# Shift_registers_circuit.net
KiCad netlist of a schematic drawn in EAGLE
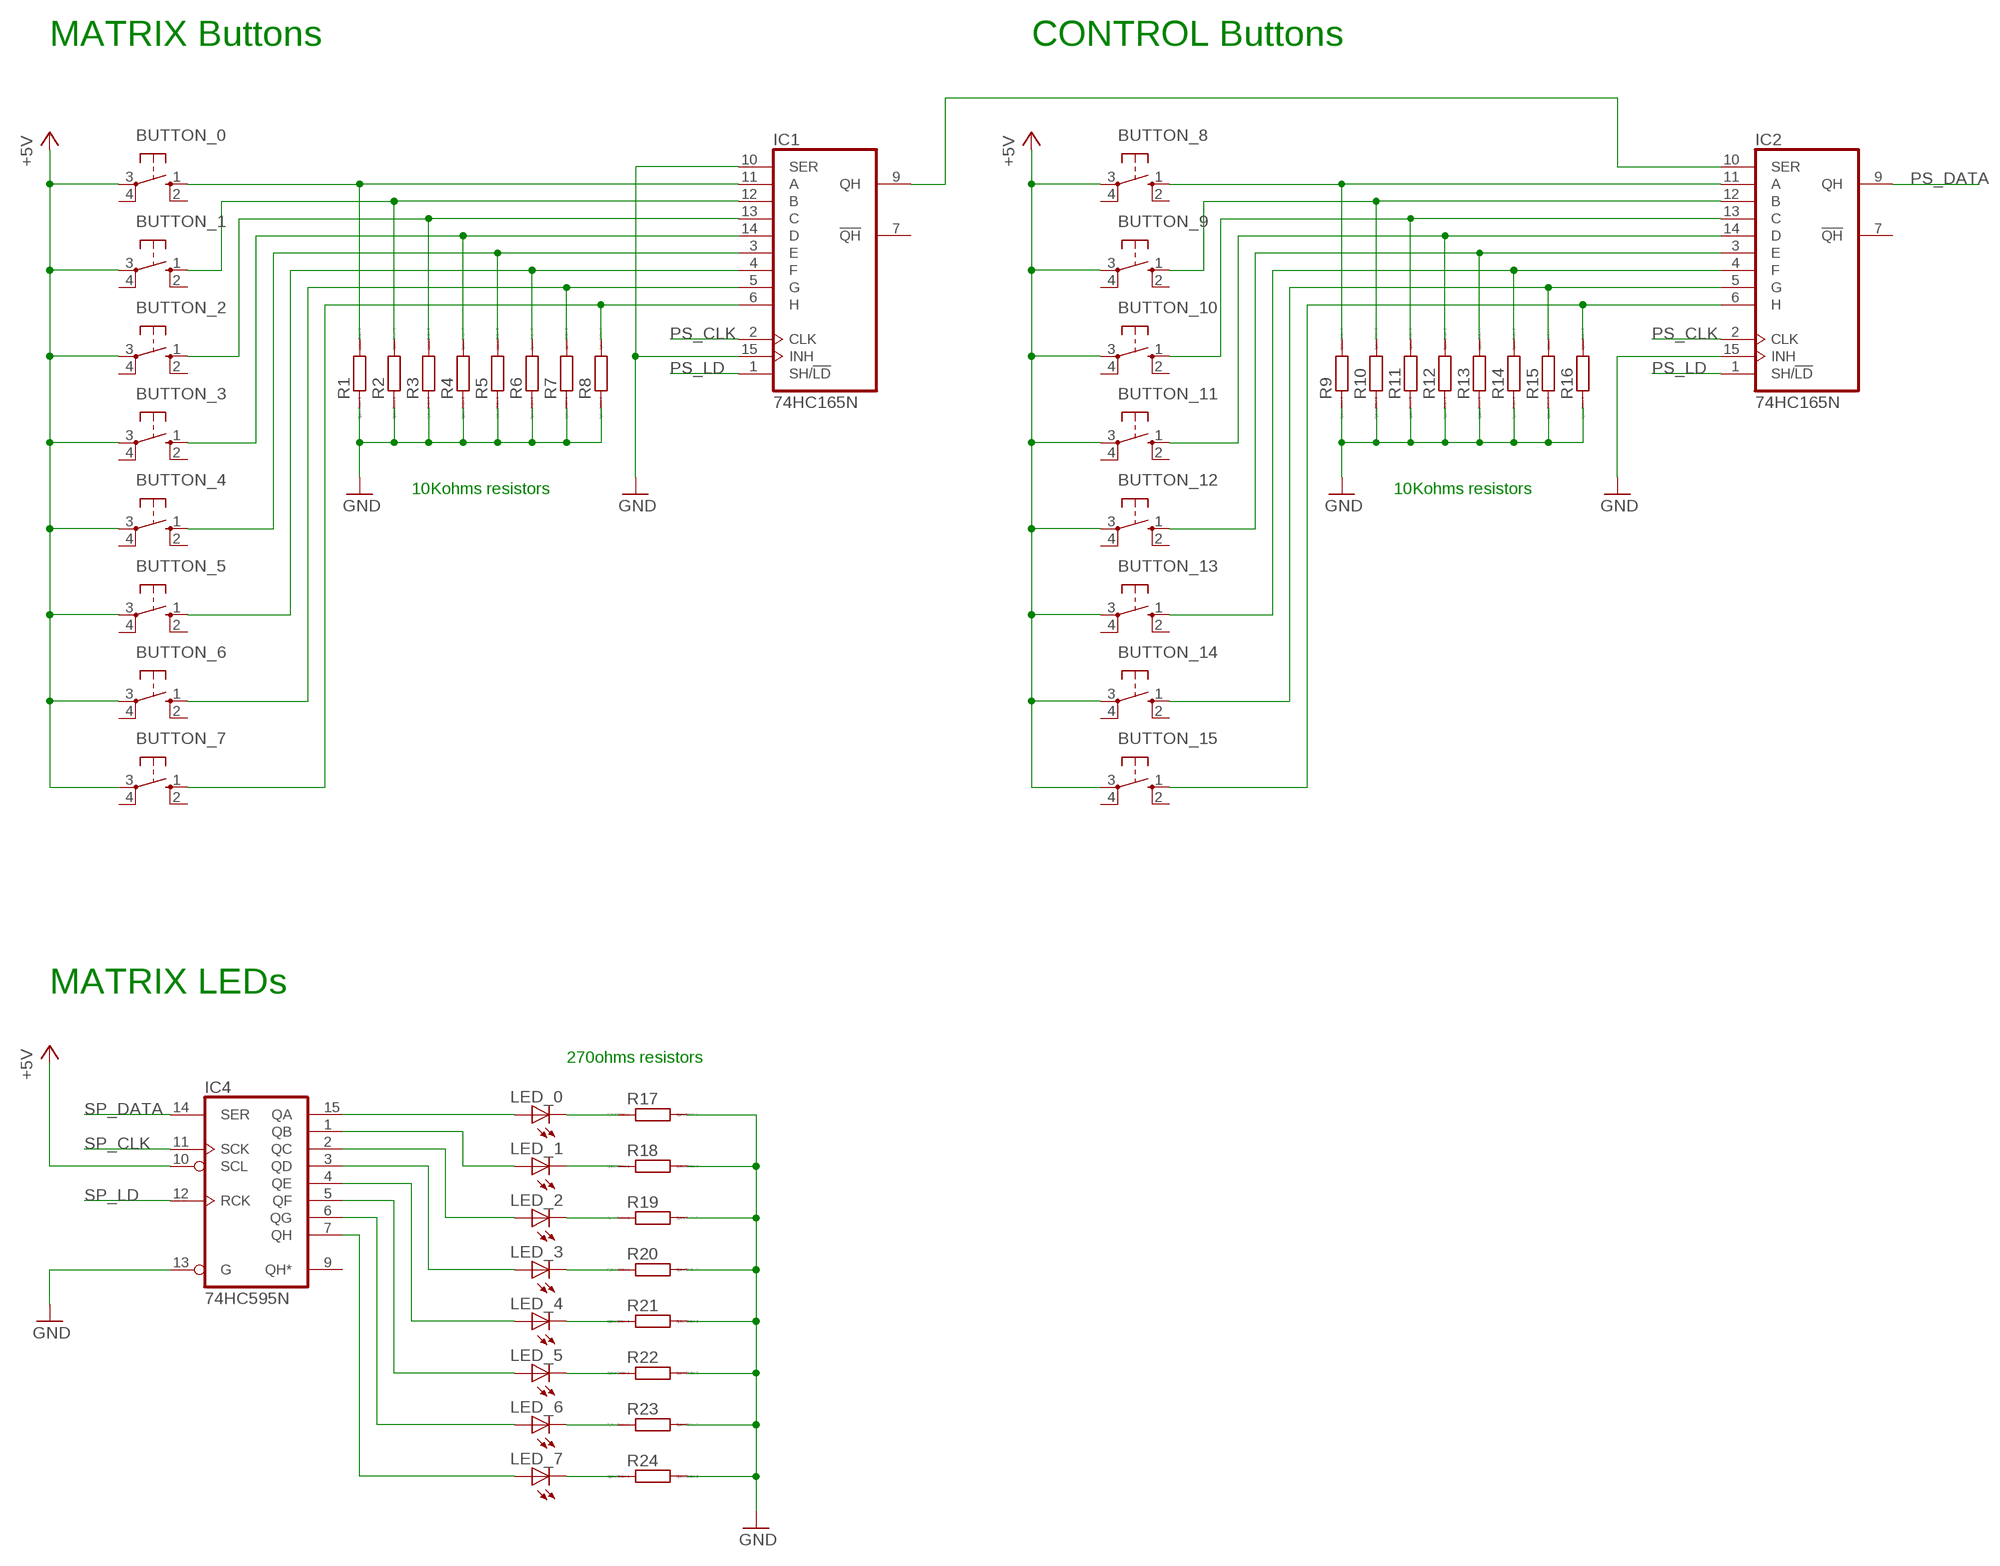
[diagram p0: schematic, sheet 1]

(export (version "E")
  (design (tool "Eeschema 10.0.6"))
  (components
    (comp (ref "BUTTON_0")
      (value "10-XX")
      (footprint "eagle-import:B3F-10XX")
      (fields (field (name "MPN") "B3F-1000"))
      (libsource (lib "eagle-import") (part "10-XX"))
    )
    (comp (ref "BUTTON_1")
      (value "10-XX")
      (footprint "eagle-import:B3F-10XX")
      (fields (field (name "MPN") "B3F-1000"))
      (libsource (lib "eagle-import") (part "10-XX"))
    )
    (comp (ref "BUTTON_2")
      (value "10-XX")
      (footprint "eagle-import:B3F-10XX")
      (fields (field (name "MPN") "B3F-1000"))
      (libsource (lib "eagle-import") (part "10-XX"))
    )
    (comp (ref "BUTTON_3")
      (value "10-XX")
      (footprint "eagle-import:B3F-10XX")
      (fields (field (name "MPN") "B3F-1000"))
      (libsource (lib "eagle-import") (part "10-XX"))
    )
    (comp (ref "BUTTON_4")
      (value "10-XX")
      (footprint "eagle-import:B3F-10XX")
      (fields (field (name "MPN") "B3F-1000"))
      (libsource (lib "eagle-import") (part "10-XX"))
    )
    (comp (ref "BUTTON_5")
      (value "10-XX")
      (footprint "eagle-import:B3F-10XX")
      (fields (field (name "MPN") "B3F-1000"))
      (libsource (lib "eagle-import") (part "10-XX"))
    )
    (comp (ref "BUTTON_6")
      (value "10-XX")
      (footprint "eagle-import:B3F-10XX")
      (fields (field (name "MPN") "B3F-1000"))
      (libsource (lib "eagle-import") (part "10-XX"))
    )
    (comp (ref "BUTTON_7")
      (value "10-XX")
      (footprint "eagle-import:B3F-10XX")
      (fields (field (name "MPN") "B3F-1000"))
      (libsource (lib "eagle-import") (part "10-XX"))
    )
    (comp (ref "BUTTON_8")
      (value "10-XX")
      (footprint "eagle-import:B3F-10XX")
      (fields (field (name "MPN") "B3F-1000"))
      (libsource (lib "eagle-import") (part "10-XX"))
    )
    (comp (ref "BUTTON_9")
      (value "10-XX")
      (footprint "eagle-import:B3F-10XX")
      (fields (field (name "MPN") "B3F-1000"))
      (libsource (lib "eagle-import") (part "10-XX"))
    )
    (comp (ref "BUTTON_10")
      (value "10-XX")
      (footprint "eagle-import:B3F-10XX")
      (fields (field (name "MPN") "B3F-1000"))
      (libsource (lib "eagle-import") (part "10-XX"))
    )
    (comp (ref "BUTTON_11")
      (value "10-XX")
      (footprint "eagle-import:B3F-10XX")
      (fields (field (name "MPN") "B3F-1000"))
      (libsource (lib "eagle-import") (part "10-XX"))
    )
    (comp (ref "BUTTON_12")
      (value "10-XX")
      (footprint "eagle-import:B3F-10XX")
      (fields (field (name "MPN") "B3F-1000"))
      (libsource (lib "eagle-import") (part "10-XX"))
    )
    (comp (ref "BUTTON_13")
      (value "10-XX")
      (footprint "eagle-import:B3F-10XX")
      (fields (field (name "MPN") "B3F-1000"))
      (libsource (lib "eagle-import") (part "10-XX"))
    )
    (comp (ref "BUTTON_14")
      (value "10-XX")
      (footprint "eagle-import:B3F-10XX")
      (fields (field (name "MPN") "B3F-1000"))
      (libsource (lib "eagle-import") (part "10-XX"))
    )
    (comp (ref "BUTTON_15")
      (value "10-XX")
      (footprint "eagle-import:B3F-10XX")
      (fields (field (name "MPN") "B3F-1000"))
      (libsource (lib "eagle-import") (part "10-XX"))
    )
    (comp (ref "IC1")
      (value "74HC165N")
      (footprint "eagle-import:DIL16")
      (libsource (lib "eagle-import") (part "74165NHC"))
    )
    (comp (ref "IC2")
      (value "74HC165N")
      (footprint "eagle-import:DIL16")
      (libsource (lib "eagle-import") (part "74165NHC"))
    )
    (comp (ref "IC4")
      (value "74HC595N")
      (footprint "eagle-import:DIL16")
      (libsource (lib "eagle-import") (part "74595NHC"))
    )
    (comp (ref "LED_0")
      (value "LED5MM")
      (footprint "eagle-import:LED5MM")
      (libsource (lib "eagle-import") (part "LED5MM"))
    )
    (comp (ref "LED_1")
      (value "LED5MM")
      (footprint "eagle-import:LED5MM")
      (libsource (lib "eagle-import") (part "LED5MM"))
    )
    (comp (ref "LED_2")
      (value "LED5MM")
      (footprint "eagle-import:LED5MM")
      (libsource (lib "eagle-import") (part "LED5MM"))
    )
    (comp (ref "LED_3")
      (value "LED5MM")
      (footprint "eagle-import:LED5MM")
      (libsource (lib "eagle-import") (part "LED5MM"))
    )
    (comp (ref "LED_4")
      (value "LED5MM")
      (footprint "eagle-import:LED5MM")
      (libsource (lib "eagle-import") (part "LED5MM"))
    )
    (comp (ref "LED_5")
      (value "LED5MM")
      (footprint "eagle-import:LED5MM")
      (libsource (lib "eagle-import") (part "LED5MM"))
    )
    (comp (ref "LED_6")
      (value "LED5MM")
      (footprint "eagle-import:LED5MM")
      (libsource (lib "eagle-import") (part "LED5MM"))
    )
    (comp (ref "LED_7")
      (value "LED5MM")
      (footprint "eagle-import:LED5MM")
      (libsource (lib "eagle-import") (part "LED5MM"))
    )
    (comp (ref "R1")
      (value "R0207/10")
      (footprint "eagle-import:0207_10")
      (libsource (lib "eagle-import") (part "R0207/10"))
    )
    (comp (ref "R2")
      (value "R0207/10")
      (footprint "eagle-import:0207_10")
      (libsource (lib "eagle-import") (part "R0207/10"))
    )
    (comp (ref "R3")
      (value "R0207/10")
      (footprint "eagle-import:0207_10")
      (libsource (lib "eagle-import") (part "R0207/10"))
    )
    (comp (ref "R4")
      (value "R0207/10")
      (footprint "eagle-import:0207_10")
      (libsource (lib "eagle-import") (part "R0207/10"))
    )
    (comp (ref "R5")
      (value "R0207/10")
      (footprint "eagle-import:0207_10")
      (libsource (lib "eagle-import") (part "R0207/10"))
    )
    (comp (ref "R6")
      (value "R0207/10")
      (footprint "eagle-import:0207_10")
      (libsource (lib "eagle-import") (part "R0207/10"))
    )
    (comp (ref "R7")
      (value "R0207/10")
      (footprint "eagle-import:0207_10")
      (libsource (lib "eagle-import") (part "R0207/10"))
    )
    (comp (ref "R8")
      (value "R0207/10")
      (footprint "eagle-import:0207_10")
      (libsource (lib "eagle-import") (part "R0207/10"))
    )
    (comp (ref "R9")
      (value "R0207/10")
      (footprint "eagle-import:0207_10")
      (libsource (lib "eagle-import") (part "R0207/10"))
    )
    (comp (ref "R10")
      (value "R0207/10")
      (footprint "eagle-import:0207_10")
      (libsource (lib "eagle-import") (part "R0207/10"))
    )
    (comp (ref "R11")
      (value "R0207/10")
      (footprint "eagle-import:0207_10")
      (libsource (lib "eagle-import") (part "R0207/10"))
    )
    (comp (ref "R12")
      (value "R0207/10")
      (footprint "eagle-import:0207_10")
      (libsource (lib "eagle-import") (part "R0207/10"))
    )
    (comp (ref "R13")
      (value "R0207/10")
      (footprint "eagle-import:0207_10")
      (libsource (lib "eagle-import") (part "R0207/10"))
    )
    (comp (ref "R14")
      (value "R0207/10")
      (footprint "eagle-import:0207_10")
      (libsource (lib "eagle-import") (part "R0207/10"))
    )
    (comp (ref "R15")
      (value "R0207/10")
      (footprint "eagle-import:0207_10")
      (libsource (lib "eagle-import") (part "R0207/10"))
    )
    (comp (ref "R16")
      (value "R0207/10")
      (footprint "eagle-import:0207_10")
      (libsource (lib "eagle-import") (part "R0207/10"))
    )
    (comp (ref "R17")
      (value "R0207/10")
      (footprint "eagle-import:0207_10")
      (libsource (lib "eagle-import") (part "R0207/10"))
    )
    (comp (ref "R18")
      (value "R0207/10")
      (footprint "eagle-import:0207_10")
      (libsource (lib "eagle-import") (part "R0207/10"))
    )
    (comp (ref "R19")
      (value "R0207/10")
      (footprint "eagle-import:0207_10")
      (libsource (lib "eagle-import") (part "R0207/10"))
    )
    (comp (ref "R20")
      (value "R0207/10")
      (footprint "eagle-import:0207_10")
      (libsource (lib "eagle-import") (part "R0207/10"))
    )
    (comp (ref "R21")
      (value "R0207/10")
      (footprint "eagle-import:0207_10")
      (libsource (lib "eagle-import") (part "R0207/10"))
    )
    (comp (ref "R22")
      (value "R0207/10")
      (footprint "eagle-import:0207_10")
      (libsource (lib "eagle-import") (part "R0207/10"))
    )
    (comp (ref "R23")
      (value "R0207/10")
      (footprint "eagle-import:0207_10")
      (libsource (lib "eagle-import") (part "R0207/10"))
    )
    (comp (ref "R24")
      (value "R0207/10")
      (footprint "eagle-import:0207_10")
      (libsource (lib "eagle-import") (part "R0207/10"))
    )
  )
  (nets
    (net (code "1") (name "+5V") (class "Default")
      (node (ref "BUTTON_0") (pin "3") (pinfunction "P_3") (pintype "passive"))
      (node (ref "BUTTON_1") (pin "3") (pinfunction "P_3") (pintype "passive"))
      (node (ref "BUTTON_10") (pin "3") (pinfunction "P_3") (pintype "passive"))
      (node (ref "BUTTON_11") (pin "3") (pinfunction "P_3") (pintype "passive"))
      (node (ref "BUTTON_12") (pin "3") (pinfunction "P_3") (pintype "passive"))
      (node (ref "BUTTON_13") (pin "3") (pinfunction "P_3") (pintype "passive"))
      (node (ref "BUTTON_14") (pin "3") (pinfunction "P_3") (pintype "passive"))
      (node (ref "BUTTON_15") (pin "3") (pinfunction "P_3") (pintype "passive"))
      (node (ref "BUTTON_2") (pin "3") (pinfunction "P_3") (pintype "passive"))
      (node (ref "BUTTON_3") (pin "3") (pinfunction "P_3") (pintype "passive"))
      (node (ref "BUTTON_4") (pin "3") (pinfunction "P_3") (pintype "passive"))
      (node (ref "BUTTON_5") (pin "3") (pinfunction "P_3") (pintype "passive"))
      (node (ref "BUTTON_6") (pin "3") (pinfunction "P_3") (pintype "passive"))
      (node (ref "BUTTON_7") (pin "3") (pinfunction "P_3") (pintype "passive"))
      (node (ref "BUTTON_8") (pin "3") (pinfunction "P_3") (pintype "passive"))
      (node (ref "BUTTON_9") (pin "3") (pinfunction "P_3") (pintype "passive"))
      (node (ref "IC4") (pin "10") (pinfunction "SCL_10") (pintype "input"))
    )
    (net (code "2") (name "/PS_CLK") (class "Default")
      (node (ref "IC1") (pin "2") (pinfunction "CLK_2") (pintype "input"))
      (node (ref "IC2") (pin "2") (pinfunction "CLK_2") (pintype "input"))
    )
    (net (code "3") (name "/PS_DATA") (class "Default")
      (node (ref "IC2") (pin "9") (pinfunction "QH_9") (pintype "output"))
    )
    (net (code "4") (name "/PS_LD") (class "Default")
      (node (ref "IC1") (pin "1") (pinfunction "SH/~{LD}_1") (pintype "input"))
      (node (ref "IC2") (pin "1") (pinfunction "SH/~{LD}_1") (pintype "input"))
    )
    (net (code "5") (name "/SP_CLK") (class "Default")
      (node (ref "IC4") (pin "11") (pinfunction "SCK_11") (pintype "input"))
    )
    (net (code "6") (name "/SP_DATA") (class "Default")
      (node (ref "IC4") (pin "14") (pinfunction "SER_14") (pintype "input"))
    )
    (net (code "7") (name "/SP_LD") (class "Default")
      (node (ref "IC4") (pin "12") (pinfunction "RCK_12") (pintype "input"))
    )
    (net (code "8") (name "GND") (class "Default")
      (node (ref "IC1") (pin "10") (pinfunction "SER_10") (pintype "input"))
      (node (ref "IC1") (pin "15") (pinfunction "INH_15") (pintype "input"))
      (node (ref "IC2") (pin "15") (pinfunction "INH_15") (pintype "input"))
      (node (ref "IC4") (pin "13") (pinfunction "G_13") (pintype "input"))
      (node (ref "R1") (pin "1") (pinfunction "1_1") (pintype "passive"))
      (node (ref "R10") (pin "1") (pinfunction "1_1") (pintype "passive"))
      (node (ref "R11") (pin "1") (pinfunction "1_1") (pintype "passive"))
      (node (ref "R12") (pin "1") (pinfunction "1_1") (pintype "passive"))
      (node (ref "R13") (pin "1") (pinfunction "1_1") (pintype "passive"))
      (node (ref "R14") (pin "1") (pinfunction "1_1") (pintype "passive"))
      (node (ref "R15") (pin "1") (pinfunction "1_1") (pintype "passive"))
      (node (ref "R16") (pin "1") (pinfunction "1_1") (pintype "passive"))
      (node (ref "R17") (pin "2") (pinfunction "2_2") (pintype "passive"))
      (node (ref "R18") (pin "2") (pinfunction "2_2") (pintype "passive"))
      (node (ref "R19") (pin "2") (pinfunction "2_2") (pintype "passive"))
      (node (ref "R2") (pin "1") (pinfunction "1_1") (pintype "passive"))
      (node (ref "R20") (pin "2") (pinfunction "2_2") (pintype "passive"))
      (node (ref "R21") (pin "2") (pinfunction "2_2") (pintype "passive"))
      (node (ref "R22") (pin "2") (pinfunction "2_2") (pintype "passive"))
      (node (ref "R23") (pin "2") (pinfunction "2_2") (pintype "passive"))
      (node (ref "R24") (pin "2") (pinfunction "2_2") (pintype "passive"))
      (node (ref "R3") (pin "1") (pinfunction "1_1") (pintype "passive"))
      (node (ref "R4") (pin "1") (pinfunction "1_1") (pintype "passive"))
      (node (ref "R5") (pin "1") (pinfunction "1_1") (pintype "passive"))
      (node (ref "R6") (pin "1") (pinfunction "1_1") (pintype "passive"))
      (node (ref "R7") (pin "1") (pinfunction "1_1") (pintype "passive"))
      (node (ref "R8") (pin "1") (pinfunction "1_1") (pintype "passive"))
      (node (ref "R9") (pin "1") (pinfunction "1_1") (pintype "passive"))
    )
    (net (code "9") (name "Net-(BUTTON_0-S)") (class "Default")
      (node (ref "BUTTON_0") (pin "1") (pinfunction "S_1") (pintype "passive"))
      (node (ref "IC1") (pin "11") (pinfunction "A_11") (pintype "input"))
      (node (ref "R1") (pin "2") (pinfunction "2_2") (pintype "passive"))
    )
    (net (code "10") (name "Net-(BUTTON_1-S)") (class "Default")
      (node (ref "BUTTON_1") (pin "1") (pinfunction "S_1") (pintype "passive"))
      (node (ref "IC1") (pin "12") (pinfunction "B_12") (pintype "input"))
      (node (ref "R2") (pin "2") (pinfunction "2_2") (pintype "passive"))
    )
    (net (code "11") (name "Net-(BUTTON_2-S)") (class "Default")
      (node (ref "BUTTON_2") (pin "1") (pinfunction "S_1") (pintype "passive"))
      (node (ref "IC1") (pin "13") (pinfunction "C_13") (pintype "input"))
      (node (ref "R3") (pin "2") (pinfunction "2_2") (pintype "passive"))
    )
    (net (code "12") (name "Net-(BUTTON_3-S)") (class "Default")
      (node (ref "BUTTON_3") (pin "1") (pinfunction "S_1") (pintype "passive"))
      (node (ref "IC1") (pin "14") (pinfunction "D_14") (pintype "input"))
      (node (ref "R4") (pin "2") (pinfunction "2_2") (pintype "passive"))
    )
    (net (code "13") (name "Net-(BUTTON_4-S)") (class "Default")
      (node (ref "BUTTON_4") (pin "1") (pinfunction "S_1") (pintype "passive"))
      (node (ref "IC1") (pin "3") (pinfunction "E_3") (pintype "input"))
      (node (ref "R5") (pin "2") (pinfunction "2_2") (pintype "passive"))
    )
    (net (code "14") (name "Net-(BUTTON_5-S)") (class "Default")
      (node (ref "BUTTON_5") (pin "1") (pinfunction "S_1") (pintype "passive"))
      (node (ref "IC1") (pin "4") (pinfunction "F_4") (pintype "input"))
      (node (ref "R6") (pin "2") (pinfunction "2_2") (pintype "passive"))
    )
    (net (code "15") (name "Net-(BUTTON_6-S)") (class "Default")
      (node (ref "BUTTON_6") (pin "1") (pinfunction "S_1") (pintype "passive"))
      (node (ref "IC1") (pin "5") (pinfunction "G_5") (pintype "input"))
      (node (ref "R7") (pin "2") (pinfunction "2_2") (pintype "passive"))
    )
    (net (code "16") (name "Net-(BUTTON_7-S)") (class "Default")
      (node (ref "BUTTON_7") (pin "1") (pinfunction "S_1") (pintype "passive"))
      (node (ref "IC1") (pin "6") (pinfunction "H_6") (pintype "input"))
      (node (ref "R8") (pin "2") (pinfunction "2_2") (pintype "passive"))
    )
    (net (code "17") (name "Net-(BUTTON_8-S)") (class "Default")
      (node (ref "BUTTON_8") (pin "1") (pinfunction "S_1") (pintype "passive"))
      (node (ref "IC2") (pin "11") (pinfunction "A_11") (pintype "input"))
      (node (ref "R9") (pin "2") (pinfunction "2_2") (pintype "passive"))
    )
    (net (code "18") (name "Net-(BUTTON_9-S)") (class "Default")
      (node (ref "BUTTON_9") (pin "1") (pinfunction "S_1") (pintype "passive"))
      (node (ref "IC2") (pin "12") (pinfunction "B_12") (pintype "input"))
      (node (ref "R10") (pin "2") (pinfunction "2_2") (pintype "passive"))
    )
    (net (code "19") (name "Net-(BUTTON_10-S)") (class "Default")
      (node (ref "BUTTON_10") (pin "1") (pinfunction "S_1") (pintype "passive"))
      (node (ref "IC2") (pin "13") (pinfunction "C_13") (pintype "input"))
      (node (ref "R11") (pin "2") (pinfunction "2_2") (pintype "passive"))
    )
    (net (code "20") (name "Net-(BUTTON_11-S)") (class "Default")
      (node (ref "BUTTON_11") (pin "1") (pinfunction "S_1") (pintype "passive"))
      (node (ref "IC2") (pin "14") (pinfunction "D_14") (pintype "input"))
      (node (ref "R12") (pin "2") (pinfunction "2_2") (pintype "passive"))
    )
    (net (code "21") (name "Net-(BUTTON_12-S)") (class "Default")
      (node (ref "BUTTON_12") (pin "1") (pinfunction "S_1") (pintype "passive"))
      (node (ref "IC2") (pin "3") (pinfunction "E_3") (pintype "input"))
      (node (ref "R13") (pin "2") (pinfunction "2_2") (pintype "passive"))
    )
    (net (code "22") (name "Net-(BUTTON_13-S)") (class "Default")
      (node (ref "BUTTON_13") (pin "1") (pinfunction "S_1") (pintype "passive"))
      (node (ref "IC2") (pin "4") (pinfunction "F_4") (pintype "input"))
      (node (ref "R14") (pin "2") (pinfunction "2_2") (pintype "passive"))
    )
    (net (code "23") (name "Net-(BUTTON_14-S)") (class "Default")
      (node (ref "BUTTON_14") (pin "1") (pinfunction "S_1") (pintype "passive"))
      (node (ref "IC2") (pin "5") (pinfunction "G_5") (pintype "input"))
      (node (ref "R15") (pin "2") (pinfunction "2_2") (pintype "passive"))
    )
    (net (code "24") (name "Net-(BUTTON_15-S)") (class "Default")
      (node (ref "BUTTON_15") (pin "1") (pinfunction "S_1") (pintype "passive"))
      (node (ref "IC2") (pin "6") (pinfunction "H_6") (pintype "input"))
      (node (ref "R16") (pin "2") (pinfunction "2_2") (pintype "passive"))
    )
    (net (code "25") (name "Net-(IC1A-QH)") (class "Default")
      (node (ref "IC1") (pin "9") (pinfunction "QH_9") (pintype "output"))
      (node (ref "IC2") (pin "10") (pinfunction "SER_10") (pintype "input"))
    )
    (net (code "26") (name "Net-(IC4A-QA)") (class "Default")
      (node (ref "IC4") (pin "15") (pinfunction "QA_15") (pintype "tri_state"))
      (node (ref "LED_0") (pin "A") (pinfunction "A_A") (pintype "passive"))
    )
    (net (code "27") (name "Net-(IC4A-QB)") (class "Default")
      (node (ref "IC4") (pin "1") (pinfunction "QB_1") (pintype "tri_state"))
      (node (ref "LED_1") (pin "A") (pinfunction "A_A") (pintype "passive"))
    )
    (net (code "28") (name "Net-(IC4A-QC)") (class "Default")
      (node (ref "IC4") (pin "2") (pinfunction "QC_2") (pintype "tri_state"))
      (node (ref "LED_2") (pin "A") (pinfunction "A_A") (pintype "passive"))
    )
    (net (code "29") (name "Net-(IC4A-QD)") (class "Default")
      (node (ref "IC4") (pin "3") (pinfunction "QD_3") (pintype "tri_state"))
      (node (ref "LED_3") (pin "A") (pinfunction "A_A") (pintype "passive"))
    )
    (net (code "30") (name "Net-(IC4A-QE)") (class "Default")
      (node (ref "IC4") (pin "4") (pinfunction "QE_4") (pintype "tri_state"))
      (node (ref "LED_4") (pin "A") (pinfunction "A_A") (pintype "passive"))
    )
    (net (code "31") (name "Net-(IC4A-QF)") (class "Default")
      (node (ref "IC4") (pin "5") (pinfunction "QF_5") (pintype "tri_state"))
      (node (ref "LED_5") (pin "A") (pinfunction "A_A") (pintype "passive"))
    )
    (net (code "32") (name "Net-(IC4A-QG)") (class "Default")
      (node (ref "IC4") (pin "6") (pinfunction "QG_6") (pintype "tri_state"))
      (node (ref "LED_6") (pin "A") (pinfunction "A_A") (pintype "passive"))
    )
    (net (code "33") (name "Net-(IC4A-QH)") (class "Default")
      (node (ref "IC4") (pin "7") (pinfunction "QH_7") (pintype "tri_state"))
      (node (ref "LED_7") (pin "A") (pinfunction "A_A") (pintype "passive"))
    )
    (net (code "34") (name "Net-(LED_0-C)") (class "Default")
      (node (ref "LED_0") (pin "K") (pinfunction "C_K") (pintype "passive"))
      (node (ref "R17") (pin "1") (pinfunction "1_1") (pintype "passive"))
    )
    (net (code "35") (name "Net-(LED_1-C)") (class "Default")
      (node (ref "LED_1") (pin "K") (pinfunction "C_K") (pintype "passive"))
      (node (ref "R18") (pin "1") (pinfunction "1_1") (pintype "passive"))
    )
    (net (code "36") (name "Net-(LED_2-C)") (class "Default")
      (node (ref "LED_2") (pin "K") (pinfunction "C_K") (pintype "passive"))
      (node (ref "R19") (pin "1") (pinfunction "1_1") (pintype "passive"))
    )
    (net (code "37") (name "Net-(LED_3-C)") (class "Default")
      (node (ref "LED_3") (pin "K") (pinfunction "C_K") (pintype "passive"))
      (node (ref "R20") (pin "1") (pinfunction "1_1") (pintype "passive"))
    )
    (net (code "38") (name "Net-(LED_4-C)") (class "Default")
      (node (ref "LED_4") (pin "K") (pinfunction "C_K") (pintype "passive"))
      (node (ref "R21") (pin "1") (pinfunction "1_1") (pintype "passive"))
    )
    (net (code "39") (name "Net-(LED_5-C)") (class "Default")
      (node (ref "LED_5") (pin "K") (pinfunction "C_K") (pintype "passive"))
      (node (ref "R22") (pin "1") (pinfunction "1_1") (pintype "passive"))
    )
    (net (code "40") (name "Net-(LED_6-C)") (class "Default")
      (node (ref "LED_6") (pin "K") (pinfunction "C_K") (pintype "passive"))
      (node (ref "R23") (pin "1") (pinfunction "1_1") (pintype "passive"))
    )
    (net (code "41") (name "Net-(LED_7-C)") (class "Default")
      (node (ref "LED_7") (pin "K") (pinfunction "C_K") (pintype "passive"))
      (node (ref "R24") (pin "1") (pinfunction "1_1") (pintype "passive"))
    )
    (net (code "42") (name "unconnected-(BUTTON_0-P1-Pad4)") (class "Default")
      (node (ref "BUTTON_0") (pin "4") (pinfunction "P1_4") (pintype "passive"))
    )
    (net (code "43") (name "unconnected-(BUTTON_0-S1-Pad2)") (class "Default")
      (node (ref "BUTTON_0") (pin "2") (pinfunction "S1_2") (pintype "passive"))
    )
    (net (code "44") (name "unconnected-(BUTTON_1-P1-Pad4)") (class "Default")
      (node (ref "BUTTON_1") (pin "4") (pinfunction "P1_4") (pintype "passive"))
    )
    (net (code "45") (name "unconnected-(BUTTON_1-S1-Pad2)") (class "Default")
      (node (ref "BUTTON_1") (pin "2") (pinfunction "S1_2") (pintype "passive"))
    )
    (net (code "46") (name "unconnected-(BUTTON_2-P1-Pad4)") (class "Default")
      (node (ref "BUTTON_2") (pin "4") (pinfunction "P1_4") (pintype "passive"))
    )
    (net (code "47") (name "unconnected-(BUTTON_2-S1-Pad2)") (class "Default")
      (node (ref "BUTTON_2") (pin "2") (pinfunction "S1_2") (pintype "passive"))
    )
    (net (code "48") (name "unconnected-(BUTTON_3-P1-Pad4)") (class "Default")
      (node (ref "BUTTON_3") (pin "4") (pinfunction "P1_4") (pintype "passive"))
    )
    (net (code "49") (name "unconnected-(BUTTON_3-S1-Pad2)") (class "Default")
      (node (ref "BUTTON_3") (pin "2") (pinfunction "S1_2") (pintype "passive"))
    )
    (net (code "50") (name "unconnected-(BUTTON_4-P1-Pad4)") (class "Default")
      (node (ref "BUTTON_4") (pin "4") (pinfunction "P1_4") (pintype "passive"))
    )
    (net (code "51") (name "unconnected-(BUTTON_4-S1-Pad2)") (class "Default")
      (node (ref "BUTTON_4") (pin "2") (pinfunction "S1_2") (pintype "passive"))
    )
    (net (code "52") (name "unconnected-(BUTTON_5-P1-Pad4)") (class "Default")
      (node (ref "BUTTON_5") (pin "4") (pinfunction "P1_4") (pintype "passive"))
    )
    (net (code "53") (name "unconnected-(BUTTON_5-S1-Pad2)") (class "Default")
      (node (ref "BUTTON_5") (pin "2") (pinfunction "S1_2") (pintype "passive"))
    )
    (net (code "54") (name "unconnected-(BUTTON_6-P1-Pad4)") (class "Default")
      (node (ref "BUTTON_6") (pin "4") (pinfunction "P1_4") (pintype "passive"))
    )
    (net (code "55") (name "unconnected-(BUTTON_6-S1-Pad2)") (class "Default")
      (node (ref "BUTTON_6") (pin "2") (pinfunction "S1_2") (pintype "passive"))
    )
    (net (code "56") (name "unconnected-(BUTTON_7-P1-Pad4)") (class "Default")
      (node (ref "BUTTON_7") (pin "4") (pinfunction "P1_4") (pintype "passive"))
    )
    (net (code "57") (name "unconnected-(BUTTON_7-S1-Pad2)") (class "Default")
      (node (ref "BUTTON_7") (pin "2") (pinfunction "S1_2") (pintype "passive"))
    )
    (net (code "58") (name "unconnected-(BUTTON_8-P1-Pad4)") (class "Default")
      (node (ref "BUTTON_8") (pin "4") (pinfunction "P1_4") (pintype "passive"))
    )
    (net (code "59") (name "unconnected-(BUTTON_8-S1-Pad2)") (class "Default")
      (node (ref "BUTTON_8") (pin "2") (pinfunction "S1_2") (pintype "passive"))
    )
    (net (code "60") (name "unconnected-(BUTTON_9-P1-Pad4)") (class "Default")
      (node (ref "BUTTON_9") (pin "4") (pinfunction "P1_4") (pintype "passive"))
    )
    (net (code "61") (name "unconnected-(BUTTON_9-S1-Pad2)") (class "Default")
      (node (ref "BUTTON_9") (pin "2") (pinfunction "S1_2") (pintype "passive"))
    )
    (net (code "62") (name "unconnected-(BUTTON_10-P1-Pad4)") (class "Default")
      (node (ref "BUTTON_10") (pin "4") (pinfunction "P1_4") (pintype "passive"))
    )
    (net (code "63") (name "unconnected-(BUTTON_10-S1-Pad2)") (class "Default")
      (node (ref "BUTTON_10") (pin "2") (pinfunction "S1_2") (pintype "passive"))
    )
    (net (code "64") (name "unconnected-(BUTTON_11-P1-Pad4)") (class "Default")
      (node (ref "BUTTON_11") (pin "4") (pinfunction "P1_4") (pintype "passive"))
    )
    (net (code "65") (name "unconnected-(BUTTON_11-S1-Pad2)") (class "Default")
      (node (ref "BUTTON_11") (pin "2") (pinfunction "S1_2") (pintype "passive"))
    )
    (net (code "66") (name "unconnected-(BUTTON_12-P1-Pad4)") (class "Default")
      (node (ref "BUTTON_12") (pin "4") (pinfunction "P1_4") (pintype "passive"))
    )
    (net (code "67") (name "unconnected-(BUTTON_12-S1-Pad2)") (class "Default")
      (node (ref "BUTTON_12") (pin "2") (pinfunction "S1_2") (pintype "passive"))
    )
    (net (code "68") (name "unconnected-(BUTTON_13-P1-Pad4)") (class "Default")
      (node (ref "BUTTON_13") (pin "4") (pinfunction "P1_4") (pintype "passive"))
    )
    (net (code "69") (name "unconnected-(BUTTON_13-S1-Pad2)") (class "Default")
      (node (ref "BUTTON_13") (pin "2") (pinfunction "S1_2") (pintype "passive"))
    )
    (net (code "70") (name "unconnected-(BUTTON_14-P1-Pad4)") (class "Default")
      (node (ref "BUTTON_14") (pin "4") (pinfunction "P1_4") (pintype "passive"))
    )
    (net (code "71") (name "unconnected-(BUTTON_14-S1-Pad2)") (class "Default")
      (node (ref "BUTTON_14") (pin "2") (pinfunction "S1_2") (pintype "passive"))
    )
    (net (code "72") (name "unconnected-(BUTTON_15-P1-Pad4)") (class "Default")
      (node (ref "BUTTON_15") (pin "4") (pinfunction "P1_4") (pintype "passive"))
    )
    (net (code "73") (name "unconnected-(BUTTON_15-S1-Pad2)") (class "Default")
      (node (ref "BUTTON_15") (pin "2") (pinfunction "S1_2") (pintype "passive"))
    )
    (net (code "74") (name "unconnected-(IC1A-~{QH}-Pad7)") (class "Default")
      (node (ref "IC1") (pin "7") (pinfunction "~{QH}_7") (pintype "output"))
    )
    (net (code "75") (name "unconnected-(IC2A-~{QH}-Pad7)") (class "Default")
      (node (ref "IC2") (pin "7") (pinfunction "~{QH}_7") (pintype "output"))
    )
    (net (code "76") (name "unconnected-(IC4A-QH*-Pad9)") (class "Default")
      (node (ref "IC4") (pin "9") (pinfunction "QH*_9") (pintype "tri_state"))
    )
  )
)
